# stm32f765-M7.net
KiCad netlist of a schematic drawn in EAGLE
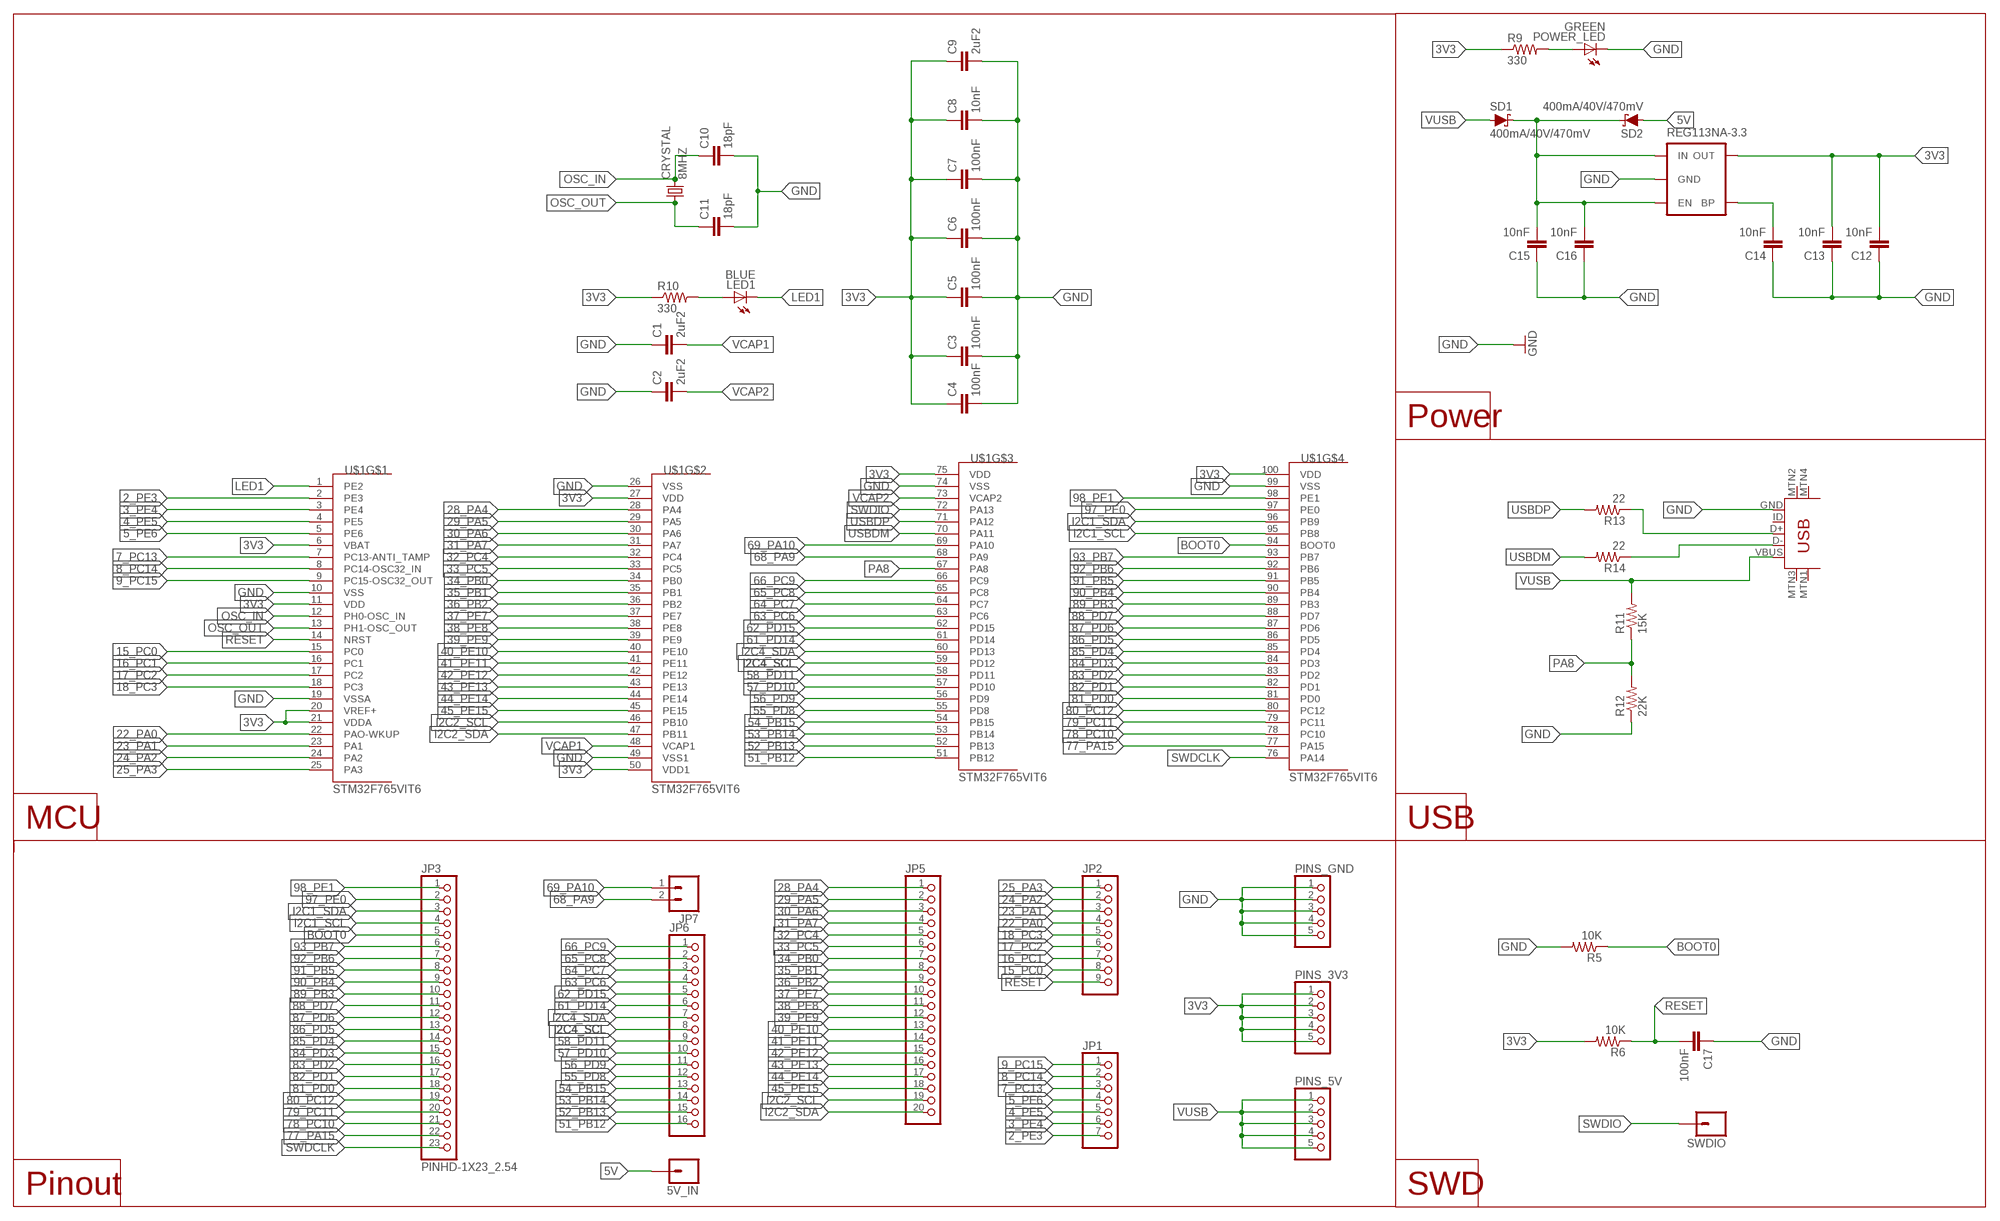
[diagram p0: schematic, sheet 1]

(export (version "E")
  (design (tool "Eeschema 10.0.6"))
  (components
    (comp (ref "5V_IN")
      (value "M01PTH_LONGPAD")
      (footprint "eagle-import:1X01_LONGPAD")
      (libsource (lib "eagle-import") (part "M01PTH_LONGPAD"))
    )
    (comp (ref "C1")
      (value "2uF2")
      (footprint "eagle-import:1206")
      (libsource (lib "eagle-import") (part "CAP1206"))
    )
    (comp (ref "C2")
      (value "2uF2")
      (footprint "eagle-import:1206")
      (libsource (lib "eagle-import") (part "CAP1206"))
    )
    (comp (ref "C3")
      (value "100nF")
      (footprint "eagle-import:1206")
      (libsource (lib "eagle-import") (part "CAP1206"))
    )
    (comp (ref "C4")
      (value "100nF")
      (footprint "eagle-import:1206")
      (libsource (lib "eagle-import") (part "CAP1206"))
    )
    (comp (ref "C5")
      (value "100nF")
      (footprint "eagle-import:1206")
      (libsource (lib "eagle-import") (part "CAP1206"))
    )
    (comp (ref "C6")
      (value "100nF")
      (footprint "eagle-import:1206")
      (libsource (lib "eagle-import") (part "CAP1206"))
    )
    (comp (ref "C7")
      (value "100nF")
      (footprint "eagle-import:1206")
      (libsource (lib "eagle-import") (part "CAP1206"))
    )
    (comp (ref "C8")
      (value "10nF")
      (footprint "eagle-import:1206")
      (libsource (lib "eagle-import") (part "CAP1206"))
    )
    (comp (ref "C9")
      (value "2uF2")
      (footprint "eagle-import:1206")
      (libsource (lib "eagle-import") (part "CAP1206"))
    )
    (comp (ref "C10")
      (value "18pF")
      (footprint "eagle-import:1206")
      (libsource (lib "eagle-import") (part "CAP1206"))
    )
    (comp (ref "C11")
      (value "18pF")
      (footprint "eagle-import:1206")
      (libsource (lib "eagle-import") (part "CAP1206"))
    )
    (comp (ref "C12")
      (value "10nF")
      (footprint "eagle-import:1206")
      (libsource (lib "eagle-import") (part "CAP1206"))
    )
    (comp (ref "C13")
      (value "10nF")
      (footprint "eagle-import:1206")
      (libsource (lib "eagle-import") (part "CAP1206"))
    )
    (comp (ref "C14")
      (value "10nF")
      (footprint "eagle-import:1206")
      (libsource (lib "eagle-import") (part "CAP1206"))
    )
    (comp (ref "C15")
      (value "10nF")
      (footprint "eagle-import:1206")
      (libsource (lib "eagle-import") (part "CAP1206"))
    )
    (comp (ref "C16")
      (value "10nF")
      (footprint "eagle-import:1206")
      (libsource (lib "eagle-import") (part "CAP1206"))
    )
    (comp (ref "C17")
      (value "100nF")
      (footprint "eagle-import:1206")
      (libsource (lib "eagle-import") (part "CAP1206"))
    )
    (comp (ref "CRYSTAL")
      (value "8MHZ")
      (footprint "eagle-import:CSM-7X-DU")
      (libsource (lib "eagle-import") (part "CSM-7X-DU"))
    )
    (comp (ref "JP1")
      (value "PINHD-1X07_2.54")
      (footprint "eagle-import:1X07")
      (libsource (lib "eagle-import") (part "PINHD-1X07_2.54"))
    )
    (comp (ref "JP2")
      (value "PINHD-1X09_2.54")
      (footprint "eagle-import:1X09")
      (libsource (lib "eagle-import") (part "PINHD-1X09_2.54"))
    )
    (comp (ref "JP3")
      (value "PINHD-1X23_2.54")
      (footprint "eagle-import:1X23")
      (libsource (lib "eagle-import") (part "PINHD-1X23_2.54"))
    )
    (comp (ref "JP5")
      (value "PINHD-1X20_2.54")
      (footprint "eagle-import:1X20")
      (libsource (lib "eagle-import") (part "PINHD-1X20_2.54"))
    )
    (comp (ref "JP6")
      (value "PINHD-1X16_2.54")
      (footprint "eagle-import:1X16")
      (libsource (lib "eagle-import") (part "PINHD-1X16_2.54"))
    )
    (comp (ref "JP7")
      (value "M02")
      (footprint "eagle-import:1X02_LONGPADS")
      (libsource (lib "eagle-import") (part "M02"))
    )
    (comp (ref "LED1")
      (value "BLUE")
      (footprint "eagle-import:1206")
      (libsource (lib "eagle-import") (part "LED1206"))
    )
    (comp (ref "PINS_3V3")
      (value "PINHD-1X05_2.54")
      (footprint "eagle-import:1X05")
      (libsource (lib "eagle-import") (part "PINHD-1X05_2.54"))
    )
    (comp (ref "PINS_5V")
      (value "PINHD-1X05_2.54")
      (footprint "eagle-import:1X05")
      (libsource (lib "eagle-import") (part "PINHD-1X05_2.54"))
    )
    (comp (ref "PINS_GND")
      (value "PINHD-1X05_2.54")
      (footprint "eagle-import:1X05")
      (libsource (lib "eagle-import") (part "PINHD-1X05_2.54"))
    )
    (comp (ref "POWER_LED")
      (value "GREEN")
      (footprint "eagle-import:1206")
      (libsource (lib "eagle-import") (part "LED1206"))
    )
    (comp (ref "R5")
      (value "10K")
      (footprint "eagle-import:1206")
      (libsource (lib "eagle-import") (part "RESISTOR1206"))
    )
    (comp (ref "R6")
      (value "10K")
      (footprint "eagle-import:1206")
      (libsource (lib "eagle-import") (part "RESISTOR1206"))
    )
    (comp (ref "R9")
      (value "330")
      (footprint "eagle-import:1206")
      (libsource (lib "eagle-import") (part "RESISTOR1206"))
    )
    (comp (ref "R10")
      (value "330")
      (footprint "eagle-import:1206")
      (libsource (lib "eagle-import") (part "RESISTOR1206"))
    )
    (comp (ref "R11")
      (value "15K")
      (footprint "eagle-import:1206")
      (libsource (lib "eagle-import") (part "RESISTOR1206"))
    )
    (comp (ref "R12")
      (value "22K")
      (footprint "eagle-import:1206")
      (libsource (lib "eagle-import") (part "RESISTOR1206"))
    )
    (comp (ref "R13")
      (value "22")
      (footprint "eagle-import:1206")
      (libsource (lib "eagle-import") (part "RESISTOR1206"))
    )
    (comp (ref "R14")
      (value "22")
      (footprint "eagle-import:1206")
      (libsource (lib "eagle-import") (part "RESISTOR1206"))
    )
    (comp (ref "REG113NA-3.3")
      (value "V_REG_LDOSMD")
      (footprint "eagle-import:SOT23-5")
      (libsource (lib "eagle-import") (part "V_REG_LDOSMD"))
    )
    (comp (ref "SD1")
      (value "400mA/40V/470mV")
      (footprint "eagle-import:SOT23-3")
      (libsource (lib "eagle-import") (part "DIODE-SCHOTTKY-ZLLS500"))
    )
    (comp (ref "SD2")
      (value "400mA/40V/470mV")
      (footprint "eagle-import:SOT23-3")
      (libsource (lib "eagle-import") (part "DIODE-SCHOTTKY-ZLLS500"))
    )
    (comp (ref "SWDIO")
      (value "M01PTH_LONGPAD")
      (footprint "eagle-import:1X01_LONGPAD")
      (libsource (lib "eagle-import") (part "M01PTH_LONGPAD"))
    )
    (comp (ref "U$1")
      (value "STM32F765VIT6")
      (footprint "eagle-import:LQFP100")
      (libsource (lib "eagle-import") (part "STM32F765VIT6"))
    )
    (comp (ref "U$7")
      (value "USB-MINIB-5PIN")
      (footprint "eagle-import:USB-MINIB")
      (libsource (lib "eagle-import") (part "USB-MINIB-5PIN"))
    )
  )
  (nets
    (net (code "1") (name "2_PE3") (class "Default")
      (node (ref "JP1") (pin "7") (pinfunction "7_7") (pintype "passive"))
      (node (ref "U$1") (pin "2") (pinfunction "PE3_2") (pintype "bidirectional"))
    )
    (net (code "2") (name "3V3") (class "Default")
      (node (ref "C12") (pin "2") (pinfunction "2_2") (pintype "passive"))
      (node (ref "C13") (pin "2") (pinfunction "2_2") (pintype "passive"))
      (node (ref "C3") (pin "1") (pinfunction "1_1") (pintype "passive"))
      (node (ref "C4") (pin "1") (pinfunction "1_1") (pintype "passive"))
      (node (ref "C5") (pin "1") (pinfunction "1_1") (pintype "passive"))
      (node (ref "C6") (pin "1") (pinfunction "1_1") (pintype "passive"))
      (node (ref "C7") (pin "1") (pinfunction "1_1") (pintype "passive"))
      (node (ref "C8") (pin "1") (pinfunction "1_1") (pintype "passive"))
      (node (ref "C9") (pin "1") (pinfunction "1_1") (pintype "passive"))
      (node (ref "PINS_3V3") (pin "1") (pinfunction "1_1") (pintype "passive"))
      (node (ref "PINS_3V3") (pin "2") (pinfunction "2_2") (pintype "passive"))
      (node (ref "PINS_3V3") (pin "3") (pinfunction "3_3") (pintype "passive"))
      (node (ref "PINS_3V3") (pin "4") (pinfunction "4_4") (pintype "passive"))
      (node (ref "PINS_3V3") (pin "5") (pinfunction "5_5") (pintype "passive"))
      (node (ref "R10") (pin "1") (pinfunction "1_1") (pintype "passive"))
      (node (ref "R6") (pin "2") (pinfunction "2_2") (pintype "passive"))
      (node (ref "R9") (pin "1") (pinfunction "1_1") (pintype "passive"))
      (node (ref "REG113NA-3.3") (pin "5") (pinfunction "OUT_5") (pintype "passive"))
      (node (ref "U$1") (pin "100") (pinfunction "VDD_100") (pintype "bidirectional"))
      (node (ref "U$1") (pin "11") (pinfunction "VDD_11") (pintype "bidirectional"))
      (node (ref "U$1") (pin "20") (pinfunction "VREF+_20") (pintype "bidirectional"))
      (node (ref "U$1") (pin "21") (pinfunction "VDDA_21") (pintype "bidirectional"))
      (node (ref "U$1") (pin "27") (pinfunction "VDD_27") (pintype "bidirectional"))
      (node (ref "U$1") (pin "50") (pinfunction "VDD1_50") (pintype "bidirectional"))
      (node (ref "U$1") (pin "6") (pinfunction "VBAT_6") (pintype "bidirectional"))
      (node (ref "U$1") (pin "75") (pinfunction "VDD_75") (pintype "bidirectional"))
    )
    (net (code "3") (name "3_PE4") (class "Default")
      (node (ref "JP1") (pin "6") (pinfunction "6_6") (pintype "passive"))
      (node (ref "U$1") (pin "3") (pinfunction "PE4_3") (pintype "bidirectional"))
    )
    (net (code "4") (name "4_PE5") (class "Default")
      (node (ref "JP1") (pin "5") (pinfunction "5_5") (pintype "passive"))
      (node (ref "U$1") (pin "4") (pinfunction "PE5_4") (pintype "bidirectional"))
    )
    (net (code "5") (name "5V") (class "Default")
      (node (ref "5V_IN") (pin "1") (pinfunction "1_1") (pintype "passive"))
      (node (ref "SD2") (pin "1") (pinfunction "A_1") (pintype "passive"))
    )
    (net (code "6") (name "5_PE6") (class "Default")
      (node (ref "JP1") (pin "4") (pinfunction "4_4") (pintype "passive"))
      (node (ref "U$1") (pin "5") (pinfunction "PE6_5") (pintype "bidirectional"))
    )
    (net (code "7") (name "7_PC13") (class "Default")
      (node (ref "JP1") (pin "3") (pinfunction "3_3") (pintype "passive"))
      (node (ref "U$1") (pin "7") (pinfunction "PC13-ANTI_TAMP_7") (pintype "bidirectional"))
    )
    (net (code "8") (name "8_PC14") (class "Default")
      (node (ref "JP1") (pin "2") (pinfunction "2_2") (pintype "passive"))
      (node (ref "U$1") (pin "8") (pinfunction "PC14-OSC32_IN_8") (pintype "bidirectional"))
    )
    (net (code "9") (name "9_PC15") (class "Default")
      (node (ref "JP1") (pin "1") (pinfunction "1_1") (pintype "passive"))
      (node (ref "U$1") (pin "9") (pinfunction "PC15-OSC32_OUT_9") (pintype "bidirectional"))
    )
    (net (code "10") (name "15_PC0") (class "Default")
      (node (ref "JP2") (pin "8") (pinfunction "8_8") (pintype "passive"))
      (node (ref "U$1") (pin "15") (pinfunction "PC0_15") (pintype "bidirectional"))
    )
    (net (code "11") (name "16_PC1") (class "Default")
      (node (ref "JP2") (pin "7") (pinfunction "7_7") (pintype "passive"))
      (node (ref "U$1") (pin "16") (pinfunction "PC1_16") (pintype "bidirectional"))
    )
    (net (code "12") (name "17_PC2") (class "Default")
      (node (ref "JP2") (pin "6") (pinfunction "6_6") (pintype "passive"))
      (node (ref "U$1") (pin "17") (pinfunction "PC2_17") (pintype "bidirectional"))
    )
    (net (code "13") (name "18_PC3") (class "Default")
      (node (ref "JP2") (pin "5") (pinfunction "5_5") (pintype "passive"))
      (node (ref "U$1") (pin "18") (pinfunction "PC3_18") (pintype "bidirectional"))
    )
    (net (code "14") (name "22_PA0") (class "Default")
      (node (ref "JP2") (pin "4") (pinfunction "4_4") (pintype "passive"))
      (node (ref "U$1") (pin "22") (pinfunction "PAO-WKUP_22") (pintype "bidirectional"))
    )
    (net (code "15") (name "23_PA1") (class "Default")
      (node (ref "JP2") (pin "3") (pinfunction "3_3") (pintype "passive"))
      (node (ref "U$1") (pin "23") (pinfunction "PA1_23") (pintype "bidirectional"))
    )
    (net (code "16") (name "24_PA2") (class "Default")
      (node (ref "JP2") (pin "2") (pinfunction "2_2") (pintype "passive"))
      (node (ref "U$1") (pin "24") (pinfunction "PA2_24") (pintype "bidirectional"))
    )
    (net (code "17") (name "25_PA3") (class "Default")
      (node (ref "JP2") (pin "1") (pinfunction "1_1") (pintype "passive"))
      (node (ref "U$1") (pin "25") (pinfunction "PA3_25") (pintype "bidirectional"))
    )
    (net (code "18") (name "28_PA4") (class "Default")
      (node (ref "JP5") (pin "1") (pinfunction "1_1") (pintype "passive"))
      (node (ref "U$1") (pin "28") (pinfunction "PA4_28") (pintype "bidirectional"))
    )
    (net (code "19") (name "29_PA5") (class "Default")
      (node (ref "JP5") (pin "2") (pinfunction "2_2") (pintype "passive"))
      (node (ref "U$1") (pin "29") (pinfunction "PA5_29") (pintype "bidirectional"))
    )
    (net (code "20") (name "30_PA6") (class "Default")
      (node (ref "JP5") (pin "3") (pinfunction "3_3") (pintype "passive"))
      (node (ref "U$1") (pin "30") (pinfunction "PA6_30") (pintype "bidirectional"))
    )
    (net (code "21") (name "31_PA7") (class "Default")
      (node (ref "JP5") (pin "4") (pinfunction "4_4") (pintype "passive"))
      (node (ref "U$1") (pin "31") (pinfunction "PA7_31") (pintype "bidirectional"))
    )
    (net (code "22") (name "32_PC4") (class "Default")
      (node (ref "JP5") (pin "5") (pinfunction "5_5") (pintype "passive"))
      (node (ref "U$1") (pin "32") (pinfunction "PC4_32") (pintype "bidirectional"))
    )
    (net (code "23") (name "33_PC5") (class "Default")
      (node (ref "JP5") (pin "6") (pinfunction "6_6") (pintype "passive"))
      (node (ref "U$1") (pin "33") (pinfunction "PC5_33") (pintype "bidirectional"))
    )
    (net (code "24") (name "34_PB0") (class "Default")
      (node (ref "JP5") (pin "7") (pinfunction "7_7") (pintype "passive"))
      (node (ref "U$1") (pin "34") (pinfunction "PB0_34") (pintype "bidirectional"))
    )
    (net (code "25") (name "35_PB1") (class "Default")
      (node (ref "JP5") (pin "8") (pinfunction "8_8") (pintype "passive"))
      (node (ref "U$1") (pin "35") (pinfunction "PB1_35") (pintype "bidirectional"))
    )
    (net (code "26") (name "36_PB2") (class "Default")
      (node (ref "JP5") (pin "9") (pinfunction "9_9") (pintype "passive"))
      (node (ref "U$1") (pin "36") (pinfunction "PB2_36") (pintype "bidirectional"))
    )
    (net (code "27") (name "37_PE7") (class "Default")
      (node (ref "JP5") (pin "10") (pinfunction "10_10") (pintype "passive"))
      (node (ref "U$1") (pin "37") (pinfunction "PE7_37") (pintype "bidirectional"))
    )
    (net (code "28") (name "38_PE8") (class "Default")
      (node (ref "JP5") (pin "11") (pinfunction "11_11") (pintype "passive"))
      (node (ref "U$1") (pin "38") (pinfunction "PE8_38") (pintype "bidirectional"))
    )
    (net (code "29") (name "39_PE9") (class "Default")
      (node (ref "JP5") (pin "12") (pinfunction "12_12") (pintype "passive"))
      (node (ref "U$1") (pin "39") (pinfunction "PE9_39") (pintype "bidirectional"))
    )
    (net (code "30") (name "40_PE10") (class "Default")
      (node (ref "JP5") (pin "13") (pinfunction "13_13") (pintype "passive"))
      (node (ref "U$1") (pin "40") (pinfunction "PE10_40") (pintype "bidirectional"))
    )
    (net (code "31") (name "41_PE11") (class "Default")
      (node (ref "JP5") (pin "14") (pinfunction "14_14") (pintype "passive"))
      (node (ref "U$1") (pin "41") (pinfunction "PE11_41") (pintype "bidirectional"))
    )
    (net (code "32") (name "42_PE12") (class "Default")
      (node (ref "JP5") (pin "15") (pinfunction "15_15") (pintype "passive"))
      (node (ref "U$1") (pin "42") (pinfunction "PE12_42") (pintype "bidirectional"))
    )
    (net (code "33") (name "43_PE13") (class "Default")
      (node (ref "JP5") (pin "16") (pinfunction "16_16") (pintype "passive"))
      (node (ref "U$1") (pin "43") (pinfunction "PE13_43") (pintype "bidirectional"))
    )
    (net (code "34") (name "44_PE14") (class "Default")
      (node (ref "JP5") (pin "17") (pinfunction "17_17") (pintype "passive"))
      (node (ref "U$1") (pin "44") (pinfunction "PE14_44") (pintype "bidirectional"))
    )
    (net (code "35") (name "45_PE15") (class "Default")
      (node (ref "JP5") (pin "18") (pinfunction "18_18") (pintype "passive"))
      (node (ref "U$1") (pin "45") (pinfunction "PE15_45") (pintype "bidirectional"))
    )
    (net (code "36") (name "51_PB12") (class "Default")
      (node (ref "JP6") (pin "16") (pinfunction "16_16") (pintype "passive"))
      (node (ref "U$1") (pin "51") (pinfunction "PB12_51") (pintype "bidirectional"))
    )
    (net (code "37") (name "52_PB13") (class "Default")
      (node (ref "JP6") (pin "15") (pinfunction "15_15") (pintype "passive"))
      (node (ref "U$1") (pin "52") (pinfunction "PB13_52") (pintype "bidirectional"))
    )
    (net (code "38") (name "53_PB14") (class "Default")
      (node (ref "JP6") (pin "14") (pinfunction "14_14") (pintype "passive"))
      (node (ref "U$1") (pin "53") (pinfunction "PB14_53") (pintype "bidirectional"))
    )
    (net (code "39") (name "54_PB15") (class "Default")
      (node (ref "JP6") (pin "13") (pinfunction "13_13") (pintype "passive"))
      (node (ref "U$1") (pin "54") (pinfunction "PB15_54") (pintype "bidirectional"))
    )
    (net (code "40") (name "55_PD8") (class "Default")
      (node (ref "JP6") (pin "12") (pinfunction "12_12") (pintype "passive"))
      (node (ref "U$1") (pin "55") (pinfunction "PD8_55") (pintype "bidirectional"))
    )
    (net (code "41") (name "56_PD9") (class "Default")
      (node (ref "JP6") (pin "11") (pinfunction "11_11") (pintype "passive"))
      (node (ref "U$1") (pin "56") (pinfunction "PD9_56") (pintype "bidirectional"))
    )
    (net (code "42") (name "57_PD10") (class "Default")
      (node (ref "JP6") (pin "10") (pinfunction "10_10") (pintype "passive"))
      (node (ref "U$1") (pin "57") (pinfunction "PD10_57") (pintype "bidirectional"))
    )
    (net (code "43") (name "58_PD11") (class "Default")
      (node (ref "JP6") (pin "9") (pinfunction "9_9") (pintype "passive"))
      (node (ref "U$1") (pin "58") (pinfunction "PD11_58") (pintype "bidirectional"))
    )
    (net (code "44") (name "61_PD14") (class "Default")
      (node (ref "JP6") (pin "6") (pinfunction "6_6") (pintype "passive"))
      (node (ref "U$1") (pin "61") (pinfunction "PD14_61") (pintype "bidirectional"))
    )
    (net (code "45") (name "62_PD15") (class "Default")
      (node (ref "JP6") (pin "5") (pinfunction "5_5") (pintype "passive"))
      (node (ref "U$1") (pin "62") (pinfunction "PD15_62") (pintype "bidirectional"))
    )
    (net (code "46") (name "63_PC6") (class "Default")
      (node (ref "JP6") (pin "4") (pinfunction "4_4") (pintype "passive"))
      (node (ref "U$1") (pin "63") (pinfunction "PC6_63") (pintype "bidirectional"))
    )
    (net (code "47") (name "64_PC7") (class "Default")
      (node (ref "JP6") (pin "3") (pinfunction "3_3") (pintype "passive"))
      (node (ref "U$1") (pin "64") (pinfunction "PC7_64") (pintype "bidirectional"))
    )
    (net (code "48") (name "65_PC8") (class "Default")
      (node (ref "JP6") (pin "2") (pinfunction "2_2") (pintype "passive"))
      (node (ref "U$1") (pin "65") (pinfunction "PC8_65") (pintype "bidirectional"))
    )
    (net (code "49") (name "66_PC9") (class "Default")
      (node (ref "JP6") (pin "1") (pinfunction "1_1") (pintype "passive"))
      (node (ref "U$1") (pin "66") (pinfunction "PC9_66") (pintype "bidirectional"))
    )
    (net (code "50") (name "68_PA9") (class "Default")
      (node (ref "JP7") (pin "2") (pinfunction "2_2") (pintype "passive"))
      (node (ref "U$1") (pin "68") (pinfunction "PA9_68") (pintype "bidirectional"))
    )
    (net (code "51") (name "69_PA10") (class "Default")
      (node (ref "JP7") (pin "1") (pinfunction "1_1") (pintype "passive"))
      (node (ref "U$1") (pin "69") (pinfunction "PA10_69") (pintype "bidirectional"))
    )
    (net (code "52") (name "77_PA15") (class "Default")
      (node (ref "JP3") (pin "22") (pinfunction "22_22") (pintype "passive"))
      (node (ref "U$1") (pin "77") (pinfunction "PA15_77") (pintype "bidirectional"))
    )
    (net (code "53") (name "78_PC10") (class "Default")
      (node (ref "JP3") (pin "21") (pinfunction "21_21") (pintype "passive"))
      (node (ref "U$1") (pin "78") (pinfunction "PC10_78") (pintype "bidirectional"))
    )
    (net (code "54") (name "79_PC11") (class "Default")
      (node (ref "JP3") (pin "20") (pinfunction "20_20") (pintype "passive"))
      (node (ref "U$1") (pin "79") (pinfunction "PC11_79") (pintype "bidirectional"))
    )
    (net (code "55") (name "80_PC12") (class "Default")
      (node (ref "JP3") (pin "19") (pinfunction "19_19") (pintype "passive"))
      (node (ref "U$1") (pin "80") (pinfunction "PC12_80") (pintype "bidirectional"))
    )
    (net (code "56") (name "81_PD0") (class "Default")
      (node (ref "JP3") (pin "18") (pinfunction "18_18") (pintype "passive"))
      (node (ref "U$1") (pin "81") (pinfunction "PD0_81") (pintype "bidirectional"))
    )
    (net (code "57") (name "82_PD1") (class "Default")
      (node (ref "JP3") (pin "17") (pinfunction "17_17") (pintype "passive"))
      (node (ref "U$1") (pin "82") (pinfunction "PD1_82") (pintype "bidirectional"))
    )
    (net (code "58") (name "83_PD2") (class "Default")
      (node (ref "JP3") (pin "16") (pinfunction "16_16") (pintype "passive"))
      (node (ref "U$1") (pin "83") (pinfunction "PD2_83") (pintype "bidirectional"))
    )
    (net (code "59") (name "84_PD3") (class "Default")
      (node (ref "JP3") (pin "15") (pinfunction "15_15") (pintype "passive"))
      (node (ref "U$1") (pin "84") (pinfunction "PD3_84") (pintype "bidirectional"))
    )
    (net (code "60") (name "85_PD4") (class "Default")
      (node (ref "JP3") (pin "14") (pinfunction "14_14") (pintype "passive"))
      (node (ref "U$1") (pin "85") (pinfunction "PD4_85") (pintype "bidirectional"))
    )
    (net (code "61") (name "86_PD5") (class "Default")
      (node (ref "JP3") (pin "13") (pinfunction "13_13") (pintype "passive"))
      (node (ref "U$1") (pin "86") (pinfunction "PD5_86") (pintype "bidirectional"))
    )
    (net (code "62") (name "87_PD6") (class "Default")
      (node (ref "JP3") (pin "12") (pinfunction "12_12") (pintype "passive"))
      (node (ref "U$1") (pin "87") (pinfunction "PD6_87") (pintype "bidirectional"))
    )
    (net (code "63") (name "88_PD7") (class "Default")
      (node (ref "JP3") (pin "11") (pinfunction "11_11") (pintype "passive"))
      (node (ref "U$1") (pin "88") (pinfunction "PD7_88") (pintype "bidirectional"))
    )
    (net (code "64") (name "89_PB3") (class "Default")
      (node (ref "JP3") (pin "10") (pinfunction "10_10") (pintype "passive"))
      (node (ref "U$1") (pin "89") (pinfunction "PB3_89") (pintype "bidirectional"))
    )
    (net (code "65") (name "90_PB4") (class "Default")
      (node (ref "JP3") (pin "9") (pinfunction "9_9") (pintype "passive"))
      (node (ref "U$1") (pin "90") (pinfunction "PB4_90") (pintype "bidirectional"))
    )
    (net (code "66") (name "91_PB5") (class "Default")
      (node (ref "JP3") (pin "8") (pinfunction "8_8") (pintype "passive"))
      (node (ref "U$1") (pin "91") (pinfunction "PB5_91") (pintype "bidirectional"))
    )
    (net (code "67") (name "92_PB6") (class "Default")
      (node (ref "JP3") (pin "7") (pinfunction "7_7") (pintype "passive"))
      (node (ref "U$1") (pin "92") (pinfunction "PB6_92") (pintype "bidirectional"))
    )
    (net (code "68") (name "93_PB7") (class "Default")
      (node (ref "JP3") (pin "6") (pinfunction "6_6") (pintype "passive"))
      (node (ref "U$1") (pin "93") (pinfunction "PB7_93") (pintype "bidirectional"))
    )
    (net (code "69") (name "97_PE0") (class "Default")
      (node (ref "JP3") (pin "2") (pinfunction "2_2") (pintype "passive"))
      (node (ref "U$1") (pin "97") (pinfunction "PE0_97") (pintype "bidirectional"))
    )
    (net (code "70") (name "98_PE1") (class "Default")
      (node (ref "JP3") (pin "1") (pinfunction "1_1") (pintype "passive"))
      (node (ref "U$1") (pin "98") (pinfunction "PE1_98") (pintype "bidirectional"))
    )
    (net (code "71") (name "BOOT0") (class "Default")
      (node (ref "JP3") (pin "5") (pinfunction "5_5") (pintype "passive"))
      (node (ref "R5") (pin "1") (pinfunction "1_1") (pintype "passive"))
      (node (ref "U$1") (pin "94") (pinfunction "BOOT0_94") (pintype "bidirectional"))
    )
    (net (code "72") (name "GND") (class "Default")
      (node (ref "C1") (pin "1") (pinfunction "1_1") (pintype "passive"))
      (node (ref "C10") (pin "2") (pinfunction "2_2") (pintype "passive"))
      (node (ref "C11") (pin "2") (pinfunction "2_2") (pintype "passive"))
      (node (ref "C12") (pin "1") (pinfunction "1_1") (pintype "passive"))
      (node (ref "C13") (pin "1") (pinfunction "1_1") (pintype "passive"))
      (node (ref "C14") (pin "1") (pinfunction "1_1") (pintype "passive"))
      (node (ref "C15") (pin "1") (pinfunction "1_1") (pintype "passive"))
      (node (ref "C16") (pin "1") (pinfunction "1_1") (pintype "passive"))
      (node (ref "C17") (pin "1") (pinfunction "1_1") (pintype "passive"))
      (node (ref "C2") (pin "1") (pinfunction "1_1") (pintype "passive"))
      (node (ref "C3") (pin "2") (pinfunction "2_2") (pintype "passive"))
      (node (ref "C4") (pin "2") (pinfunction "2_2") (pintype "passive"))
      (node (ref "C5") (pin "2") (pinfunction "2_2") (pintype "passive"))
      (node (ref "C6") (pin "2") (pinfunction "2_2") (pintype "passive"))
      (node (ref "C7") (pin "2") (pinfunction "2_2") (pintype "passive"))
      (node (ref "C8") (pin "2") (pinfunction "2_2") (pintype "passive"))
      (node (ref "C9") (pin "2") (pinfunction "2_2") (pintype "passive"))
      (node (ref "PINS_GND") (pin "1") (pinfunction "1_1") (pintype "passive"))
      (node (ref "PINS_GND") (pin "2") (pinfunction "2_2") (pintype "passive"))
      (node (ref "PINS_GND") (pin "3") (pinfunction "3_3") (pintype "passive"))
      (node (ref "PINS_GND") (pin "4") (pinfunction "4_4") (pintype "passive"))
      (node (ref "PINS_GND") (pin "5") (pinfunction "5_5") (pintype "passive"))
      (node (ref "POWER_LED") (pin "2") (pinfunction "C_2") (pintype "passive"))
      (node (ref "R12") (pin "1") (pinfunction "1_1") (pintype "passive"))
      (node (ref "R5") (pin "2") (pinfunction "2_2") (pintype "passive"))
      (node (ref "REG113NA-3.3") (pin "2") (pinfunction "GND_2") (pintype "input"))
      (node (ref "U$1") (pin "10") (pinfunction "VSS_10") (pintype "bidirectional"))
      (node (ref "U$1") (pin "19") (pinfunction "VSSA_19") (pintype "bidirectional"))
      (node (ref "U$1") (pin "26") (pinfunction "VSS_26") (pintype "bidirectional"))
      (node (ref "U$1") (pin "49") (pinfunction "VSS1_49") (pintype "bidirectional"))
      (node (ref "U$1") (pin "74") (pinfunction "VSS_74") (pintype "bidirectional"))
      (node (ref "U$1") (pin "99") (pinfunction "VSS_99") (pintype "bidirectional"))
      (node (ref "U$7") (pin "GND") (pinfunction "GND_GND") (pintype "bidirectional"))
    )
    (net (code "73") (name "I2C1_SCL") (class "Default")
      (node (ref "JP3") (pin "4") (pinfunction "4_4") (pintype "passive"))
      (node (ref "U$1") (pin "95") (pinfunction "PB8_95") (pintype "bidirectional"))
    )
    (net (code "74") (name "I2C1_SDA") (class "Default")
      (node (ref "JP3") (pin "3") (pinfunction "3_3") (pintype "passive"))
      (node (ref "U$1") (pin "96") (pinfunction "PB9_96") (pintype "bidirectional"))
    )
    (net (code "75") (name "I2C2_SCL") (class "Default")
      (node (ref "JP5") (pin "19") (pinfunction "19_19") (pintype "passive"))
      (node (ref "U$1") (pin "46") (pinfunction "PB10_46") (pintype "bidirectional"))
    )
    (net (code "76") (name "I2C2_SDA") (class "Default")
      (node (ref "JP5") (pin "20") (pinfunction "20_20") (pintype "passive"))
      (node (ref "U$1") (pin "47") (pinfunction "PB11_47") (pintype "bidirectional"))
    )
    (net (code "77") (name "I2C4_SCL") (class "Default")
      (node (ref "JP6") (pin "8") (pinfunction "8_8") (pintype "passive"))
      (node (ref "U$1") (pin "59") (pinfunction "PD12_59") (pintype "bidirectional"))
    )
    (net (code "78") (name "I2C4_SDA") (class "Default")
      (node (ref "JP6") (pin "7") (pinfunction "7_7") (pintype "passive"))
      (node (ref "U$1") (pin "60") (pinfunction "PD13_60") (pintype "bidirectional"))
    )
    (net (code "79") (name "LED1") (class "Default")
      (node (ref "LED1") (pin "2") (pinfunction "C_2") (pintype "passive"))
      (node (ref "U$1") (pin "1") (pinfunction "PE2_1") (pintype "bidirectional"))
    )
    (net (code "80") (name "Net-(LED1-A)") (class "Default")
      (node (ref "LED1") (pin "1") (pinfunction "A_1") (pintype "passive"))
      (node (ref "R10") (pin "2") (pinfunction "2_2") (pintype "passive"))
    )
    (net (code "81") (name "Net-(POWER_LED-A)") (class "Default")
      (node (ref "POWER_LED") (pin "1") (pinfunction "A_1") (pintype "passive"))
      (node (ref "R9") (pin "2") (pinfunction "2_2") (pintype "passive"))
    )
    (net (code "82") (name "Net-(R13-Pad1)") (class "Default")
      (node (ref "R13") (pin "1") (pinfunction "1_1") (pintype "passive"))
      (node (ref "U$7") (pin "D+") (pinfunction "D+_D+") (pintype "bidirectional"))
    )
    (net (code "83") (name "Net-(R14-Pad1)") (class "Default")
      (node (ref "R14") (pin "1") (pinfunction "1_1") (pintype "passive"))
      (node (ref "U$7") (pin "D-") (pinfunction "D-_D-") (pintype "bidirectional"))
    )
    (net (code "84") (name "Net-(REG113NA-3.3-BP)") (class "Default")
      (node (ref "C14") (pin "2") (pinfunction "2_2") (pintype "passive"))
      (node (ref "REG113NA-3.3") (pin "4") (pinfunction "BP_4") (pintype "input"))
    )
    (net (code "85") (name "Net-(REG113NA-3.3-EN)") (class "Default")
      (node (ref "C15") (pin "2") (pinfunction "2_2") (pintype "passive"))
      (node (ref "C16") (pin "2") (pinfunction "2_2") (pintype "passive"))
      (node (ref "REG113NA-3.3") (pin "1") (pinfunction "IN_1") (pintype "input"))
      (node (ref "REG113NA-3.3") (pin "3") (pinfunction "EN_3") (pintype "input"))
      (node (ref "SD1") (pin "3") (pinfunction "C_3") (pintype "passive"))
      (node (ref "SD2") (pin "3") (pinfunction "C_3") (pintype "passive"))
    )
    (net (code "86") (name "OSC_IN") (class "Default")
      (node (ref "C10") (pin "1") (pinfunction "1_1") (pintype "passive"))
      (node (ref "CRYSTAL") (pin "2") (pinfunction "2_2") (pintype "passive"))
      (node (ref "U$1") (pin "12") (pinfunction "PH0-OSC_IN_12") (pintype "bidirectional"))
    )
    (net (code "87") (name "OSC_OUT") (class "Default")
      (node (ref "C11") (pin "1") (pinfunction "1_1") (pintype "passive"))
      (node (ref "CRYSTAL") (pin "1") (pinfunction "1_1") (pintype "passive"))
      (node (ref "U$1") (pin "13") (pinfunction "PH1-OSC_OUT_13") (pintype "bidirectional"))
    )
    (net (code "88") (name "PA8") (class "Default")
      (node (ref "R11") (pin "1") (pinfunction "1_1") (pintype "passive"))
      (node (ref "R12") (pin "2") (pinfunction "2_2") (pintype "passive"))
      (node (ref "U$1") (pin "67") (pinfunction "PA8_67") (pintype "bidirectional"))
    )
    (net (code "89") (name "RESET") (class "Default")
      (node (ref "C17") (pin "2") (pinfunction "2_2") (pintype "passive"))
      (node (ref "JP2") (pin "9") (pinfunction "9_9") (pintype "passive"))
      (node (ref "R6") (pin "1") (pinfunction "1_1") (pintype "passive"))
      (node (ref "U$1") (pin "14") (pinfunction "NRST_14") (pintype "bidirectional"))
    )
    (net (code "90") (name "SWDCLK") (class "Default")
      (node (ref "JP3") (pin "23") (pinfunction "23_23") (pintype "passive"))
      (node (ref "U$1") (pin "76") (pinfunction "PA14_76") (pintype "bidirectional"))
    )
    (net (code "91") (name "SWDIO") (class "Default")
      (node (ref "SWDIO") (pin "1") (pinfunction "1_1") (pintype "passive"))
      (node (ref "U$1") (pin "72") (pinfunction "PA13_72") (pintype "bidirectional"))
    )
    (net (code "92") (name "USBDM") (class "Default")
      (node (ref "R14") (pin "2") (pinfunction "2_2") (pintype "passive"))
      (node (ref "U$1") (pin "70") (pinfunction "PA11_70") (pintype "bidirectional"))
    )
    (net (code "93") (name "USBDP") (class "Default")
      (node (ref "R13") (pin "2") (pinfunction "2_2") (pintype "passive"))
      (node (ref "U$1") (pin "71") (pinfunction "PA12_71") (pintype "bidirectional"))
    )
    (net (code "94") (name "VCAP1") (class "Default")
      (node (ref "C1") (pin "2") (pinfunction "2_2") (pintype "passive"))
      (node (ref "U$1") (pin "48") (pinfunction "VCAP1_48") (pintype "bidirectional"))
    )
    (net (code "95") (name "VCAP2") (class "Default")
      (node (ref "C2") (pin "2") (pinfunction "2_2") (pintype "passive"))
      (node (ref "U$1") (pin "73") (pinfunction "VCAP2_73") (pintype "bidirectional"))
    )
    (net (code "96") (name "VUSB") (class "Default")
      (node (ref "PINS_5V") (pin "1") (pinfunction "1_1") (pintype "passive"))
      (node (ref "PINS_5V") (pin "2") (pinfunction "2_2") (pintype "passive"))
      (node (ref "PINS_5V") (pin "3") (pinfunction "3_3") (pintype "passive"))
      (node (ref "PINS_5V") (pin "4") (pinfunction "4_4") (pintype "passive"))
      (node (ref "PINS_5V") (pin "5") (pinfunction "5_5") (pintype "passive"))
      (node (ref "R11") (pin "2") (pinfunction "2_2") (pintype "passive"))
      (node (ref "SD1") (pin "1") (pinfunction "A_1") (pintype "passive"))
      (node (ref "U$7") (pin "VBUS") (pinfunction "VBUS_VBUS") (pintype "bidirectional"))
    )
    (net (code "97") (name "unconnected-(U$7-MTN1-PadMTN3)") (class "Default")
      (node (ref "U$7") (pin "MTN3") (pinfunction "MTN1_MTN3") (pintype "bidirectional"))
    )
    (net (code "98") (name "unconnected-(U$7-MTN2-PadMTN1)") (class "Default")
      (node (ref "U$7") (pin "MTN1") (pinfunction "MTN2_MTN1") (pintype "bidirectional"))
    )
    (net (code "99") (name "unconnected-(U$7-MTN3-PadMTN2)") (class "Default")
      (node (ref "U$7") (pin "MTN2") (pinfunction "MTN3_MTN2") (pintype "bidirectional"))
    )
    (net (code "100") (name "unconnected-(U$7-PadID)") (class "Default")
      (node (ref "U$7") (pin "ID") (pinfunction "ID_ID") (pintype "bidirectional"))
    )
    (net (code "101") (name "unconnected-(U$7-PadMTN4)") (class "Default")
      (node (ref "U$7") (pin "MTN4") (pinfunction "MTN4_MTN4") (pintype "bidirectional"))
    )
  )
)
